# WEATHER_INDICATOR.net
KiCad netlist of a schematic drawn in EAGLE
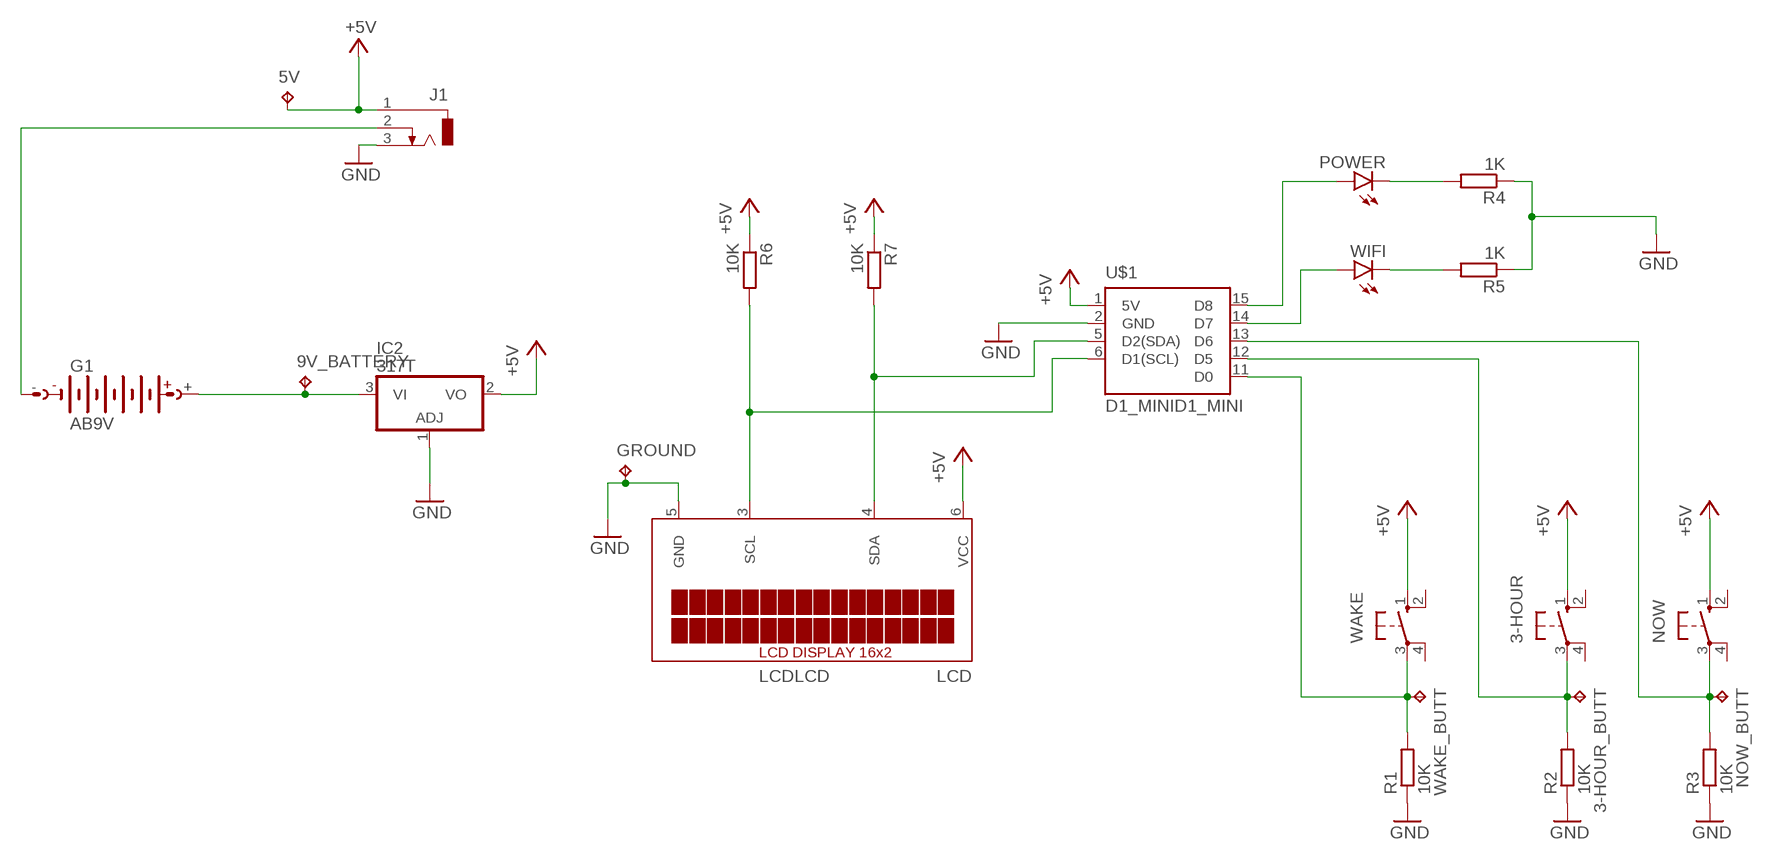
[diagram p0: schematic, sheet 1]

(export (version "E")
  (design (tool "Eeschema 10.0.6"))
  (components
    (comp (ref "3-HOUR")
      (value "10-XX")
      (footprint "eagle-import:B3F-10XX")
      (fields (field (name "MPN") "B3F-1000"))
      (libsource (lib "eagle-import") (part "10-XX"))
    )
    (comp (ref "3-HOUR_BUTT")
      (value "TPB1,27")
      (footprint "eagle-import:B1,27")
      (libsource (lib "eagle-import") (part "TPB1,27"))
    )
    (comp (ref "5V")
      (value "TPB1,27")
      (footprint "eagle-import:B1,27")
      (libsource (lib "eagle-import") (part "TPB1,27"))
    )
    (comp (ref "9V_BATTERY")
      (value "TPB1,27")
      (footprint "eagle-import:B1,27")
      (libsource (lib "eagle-import") (part "TPB1,27"))
    )
    (comp (ref "G1")
      (value "AB9V")
      (footprint "eagle-import:AB9V")
      (libsource (lib "eagle-import") (part "AB9V"))
    )
    (comp (ref "GROUND")
      (value "TPB1,27")
      (footprint "eagle-import:B1,27")
      (libsource (lib "eagle-import") (part "TPB1,27"))
    )
    (comp (ref "IC2")
      (value "317T")
      (footprint "eagle-import:TO220H")
      (libsource (lib "eagle-import") (part "317T"))
    )
    (comp (ref "J1")
      (value "DCJ0303")
      (footprint "eagle-import:DCJ0303")
      (libsource (lib "eagle-import") (part "DCJ0303"))
    )
    (comp (ref "LCD")
      (value "LCDLCD")
      (footprint "eagle-import:HDRV6W64P254_1X6_1016X508X838B")
      (libsource (lib "eagle-import") (part "LCDLCD"))
    )
    (comp (ref "NOW")
      (value "10-XX")
      (footprint "eagle-import:B3F-10XX")
      (fields (field (name "MPN") "B3F-1000"))
      (libsource (lib "eagle-import") (part "10-XX"))
    )
    (comp (ref "NOW_BUTT")
      (value "TPB1,27")
      (footprint "eagle-import:B1,27")
      (libsource (lib "eagle-import") (part "TPB1,27"))
    )
    (comp (ref "POWER")
      (value "LED3MM")
      (footprint "eagle-import:LED3MM")
      (libsource (lib "eagle-import") (part "LED3MM"))
    )
    (comp (ref "R1")
      (value "10K")
      (footprint "eagle-import:0204_7")
      (libsource (lib "eagle-import") (part "R-EU_0204/7"))
    )
    (comp (ref "R2")
      (value "10K")
      (footprint "eagle-import:0204_7")
      (libsource (lib "eagle-import") (part "R-EU_0204/7"))
    )
    (comp (ref "R3")
      (value "10K")
      (footprint "eagle-import:0204_7")
      (libsource (lib "eagle-import") (part "R-EU_0204/7"))
    )
    (comp (ref "R4")
      (value "1K")
      (footprint "eagle-import:0204_7")
      (libsource (lib "eagle-import") (part "R-EU_0204/7"))
    )
    (comp (ref "R5")
      (value "1K")
      (footprint "eagle-import:0204_7")
      (libsource (lib "eagle-import") (part "R-EU_0204/7"))
    )
    (comp (ref "R6")
      (value "10K")
      (footprint "eagle-import:0204_7")
      (libsource (lib "eagle-import") (part "R-EU_0204/7"))
    )
    (comp (ref "R7")
      (value "10K")
      (footprint "eagle-import:0204_7")
      (libsource (lib "eagle-import") (part "R-EU_0204/7"))
    )
    (comp (ref "U$1")
      (value "D1_MINID1_MINI")
      (footprint "eagle-import:DIP2540W53P254L3556H508Q16B")
      (libsource (lib "eagle-import") (part "D1_MINID1_MINI"))
    )
    (comp (ref "WAKE")
      (value "10-XX")
      (footprint "eagle-import:B3F-10XX")
      (fields (field (name "MPN") "B3F-1000"))
      (libsource (lib "eagle-import") (part "10-XX"))
    )
    (comp (ref "WAKE_BUTT")
      (value "TPB1,27")
      (footprint "eagle-import:B1,27")
      (libsource (lib "eagle-import") (part "TPB1,27"))
    )
    (comp (ref "WIFI")
      (value "LED3MM")
      (footprint "eagle-import:LED3MM")
      (libsource (lib "eagle-import") (part "LED3MM"))
    )
  )
  (nets
    (net (code "1") (name "+5V") (class "Default")
      (node (ref "3-HOUR") (pin "1") (pinfunction "S_1") (pintype "passive"))
      (node (ref "5V") (pin "TP") (pinfunction "TP_TP") (pintype "input"))
      (node (ref "IC2") (pin "2") (pinfunction "VO_2") (pintype "passive"))
      (node (ref "J1") (pin "1") (pinfunction "1_1") (pintype "passive"))
      (node (ref "LCD") (pin "6") (pinfunction "VCC_6") (pintype "power_in"))
      (node (ref "NOW") (pin "1") (pinfunction "S_1") (pintype "passive"))
      (node (ref "R6") (pin "1") (pinfunction "1_1") (pintype "passive"))
      (node (ref "R7") (pin "1") (pinfunction "1_1") (pintype "passive"))
      (node (ref "U$1") (pin "1") (pinfunction "5V_1") (pintype "input"))
      (node (ref "WAKE") (pin "1") (pinfunction "S_1") (pintype "passive"))
    )
    (net (code "2") (name "GND") (class "Default")
      (node (ref "GROUND") (pin "TP") (pinfunction "TP_TP") (pintype "input"))
      (node (ref "IC2") (pin "1") (pinfunction "ADJ_1") (pintype "input"))
      (node (ref "J1") (pin "3") (pinfunction "3_3") (pintype "passive"))
      (node (ref "LCD") (pin "5") (pinfunction "GND_5") (pintype "power_in"))
      (node (ref "R1") (pin "1") (pinfunction "1_1") (pintype "passive"))
      (node (ref "R2") (pin "1") (pinfunction "1_1") (pintype "passive"))
      (node (ref "R3") (pin "1") (pinfunction "1_1") (pintype "passive"))
      (node (ref "R4") (pin "1") (pinfunction "1_1") (pintype "passive"))
      (node (ref "R5") (pin "1") (pinfunction "1_1") (pintype "passive"))
      (node (ref "U$1") (pin "2") (pinfunction "GND_2") (pintype "input"))
    )
    (net (code "3") (name "Net-(3-HOUR-P)") (class "Default")
      (node (ref "3-HOUR") (pin "3") (pinfunction "P_3") (pintype "passive"))
      (node (ref "3-HOUR_BUTT") (pin "TP") (pinfunction "TP_TP") (pintype "input"))
      (node (ref "R2") (pin "2") (pinfunction "2_2") (pintype "passive"))
      (node (ref "U$1") (pin "12") (pinfunction "D5_12") (pintype "bidirectional"))
    )
    (net (code "4") (name "Net-(G1-Pad-)") (class "Default")
      (node (ref "G1") (pin "-") (pinfunction "-_-") (pintype "passive"))
      (node (ref "J1") (pin "2") (pinfunction "2_2") (pintype "passive"))
    )
    (net (code "5") (name "Net-(IC2-VI)") (class "Default")
      (node (ref "9V_BATTERY") (pin "TP") (pinfunction "TP_TP") (pintype "input"))
      (node (ref "G1") (pin "+") (pinfunction "+_+") (pintype "passive"))
      (node (ref "IC2") (pin "3") (pinfunction "VI_3") (pintype "input"))
    )
    (net (code "6") (name "Net-(LCD-SCL)") (class "Default")
      (node (ref "LCD") (pin "3") (pinfunction "SCL_3") (pintype "input"))
      (node (ref "R6") (pin "2") (pinfunction "2_2") (pintype "passive"))
      (node (ref "U$1") (pin "6") (pinfunction "D1(SCL)_6") (pintype "input"))
    )
    (net (code "7") (name "Net-(LCD-SDA)") (class "Default")
      (node (ref "LCD") (pin "4") (pinfunction "SDA_4") (pintype "input"))
      (node (ref "R7") (pin "2") (pinfunction "2_2") (pintype "passive"))
      (node (ref "U$1") (pin "5") (pinfunction "D2(SDA)_5") (pintype "input"))
    )
    (net (code "8") (name "Net-(NOW-P)") (class "Default")
      (node (ref "NOW") (pin "3") (pinfunction "P_3") (pintype "passive"))
      (node (ref "NOW_BUTT") (pin "TP") (pinfunction "TP_TP") (pintype "input"))
      (node (ref "R3") (pin "2") (pinfunction "2_2") (pintype "passive"))
      (node (ref "U$1") (pin "13") (pinfunction "D6_13") (pintype "bidirectional"))
    )
    (net (code "9") (name "Net-(POWER-C)") (class "Default")
      (node (ref "POWER") (pin "K") (pinfunction "C_K") (pintype "passive"))
      (node (ref "R4") (pin "2") (pinfunction "2_2") (pintype "passive"))
    )
    (net (code "10") (name "Net-(U$1-D0)") (class "Default")
      (node (ref "R1") (pin "2") (pinfunction "2_2") (pintype "passive"))
      (node (ref "U$1") (pin "11") (pinfunction "D0_11") (pintype "bidirectional"))
      (node (ref "WAKE") (pin "3") (pinfunction "P_3") (pintype "passive"))
      (node (ref "WAKE_BUTT") (pin "TP") (pinfunction "TP_TP") (pintype "input"))
    )
    (net (code "11") (name "Net-(U$1-D7)") (class "Default")
      (node (ref "U$1") (pin "14") (pinfunction "D7_14") (pintype "bidirectional"))
      (node (ref "WIFI") (pin "A") (pinfunction "A_A") (pintype "passive"))
    )
    (net (code "12") (name "Net-(U$1-D8)") (class "Default")
      (node (ref "POWER") (pin "A") (pinfunction "A_A") (pintype "passive"))
      (node (ref "U$1") (pin "15") (pinfunction "D8_15") (pintype "bidirectional"))
    )
    (net (code "13") (name "Net-(WIFI-C)") (class "Default")
      (node (ref "R5") (pin "2") (pinfunction "2_2") (pintype "passive"))
      (node (ref "WIFI") (pin "K") (pinfunction "C_K") (pintype "passive"))
    )
    (net (code "14") (name "unconnected-(3-HOUR-P1-Pad4)") (class "Default")
      (node (ref "3-HOUR") (pin "4") (pinfunction "P1_4") (pintype "passive"))
    )
    (net (code "15") (name "unconnected-(3-HOUR-S1-Pad2)") (class "Default")
      (node (ref "3-HOUR") (pin "2") (pinfunction "S1_2") (pintype "passive"))
    )
    (net (code "16") (name "unconnected-(NOW-P1-Pad4)") (class "Default")
      (node (ref "NOW") (pin "4") (pinfunction "P1_4") (pintype "passive"))
    )
    (net (code "17") (name "unconnected-(NOW-S1-Pad2)") (class "Default")
      (node (ref "NOW") (pin "2") (pinfunction "S1_2") (pintype "passive"))
    )
    (net (code "18") (name "unconnected-(WAKE-P1-Pad4)") (class "Default")
      (node (ref "WAKE") (pin "4") (pinfunction "P1_4") (pintype "passive"))
    )
    (net (code "19") (name "unconnected-(WAKE-S1-Pad2)") (class "Default")
      (node (ref "WAKE") (pin "2") (pinfunction "S1_2") (pintype "passive"))
    )
  )
)
